# MB1315A.net
KiCad netlist of a schematic drawn in Altium Designer
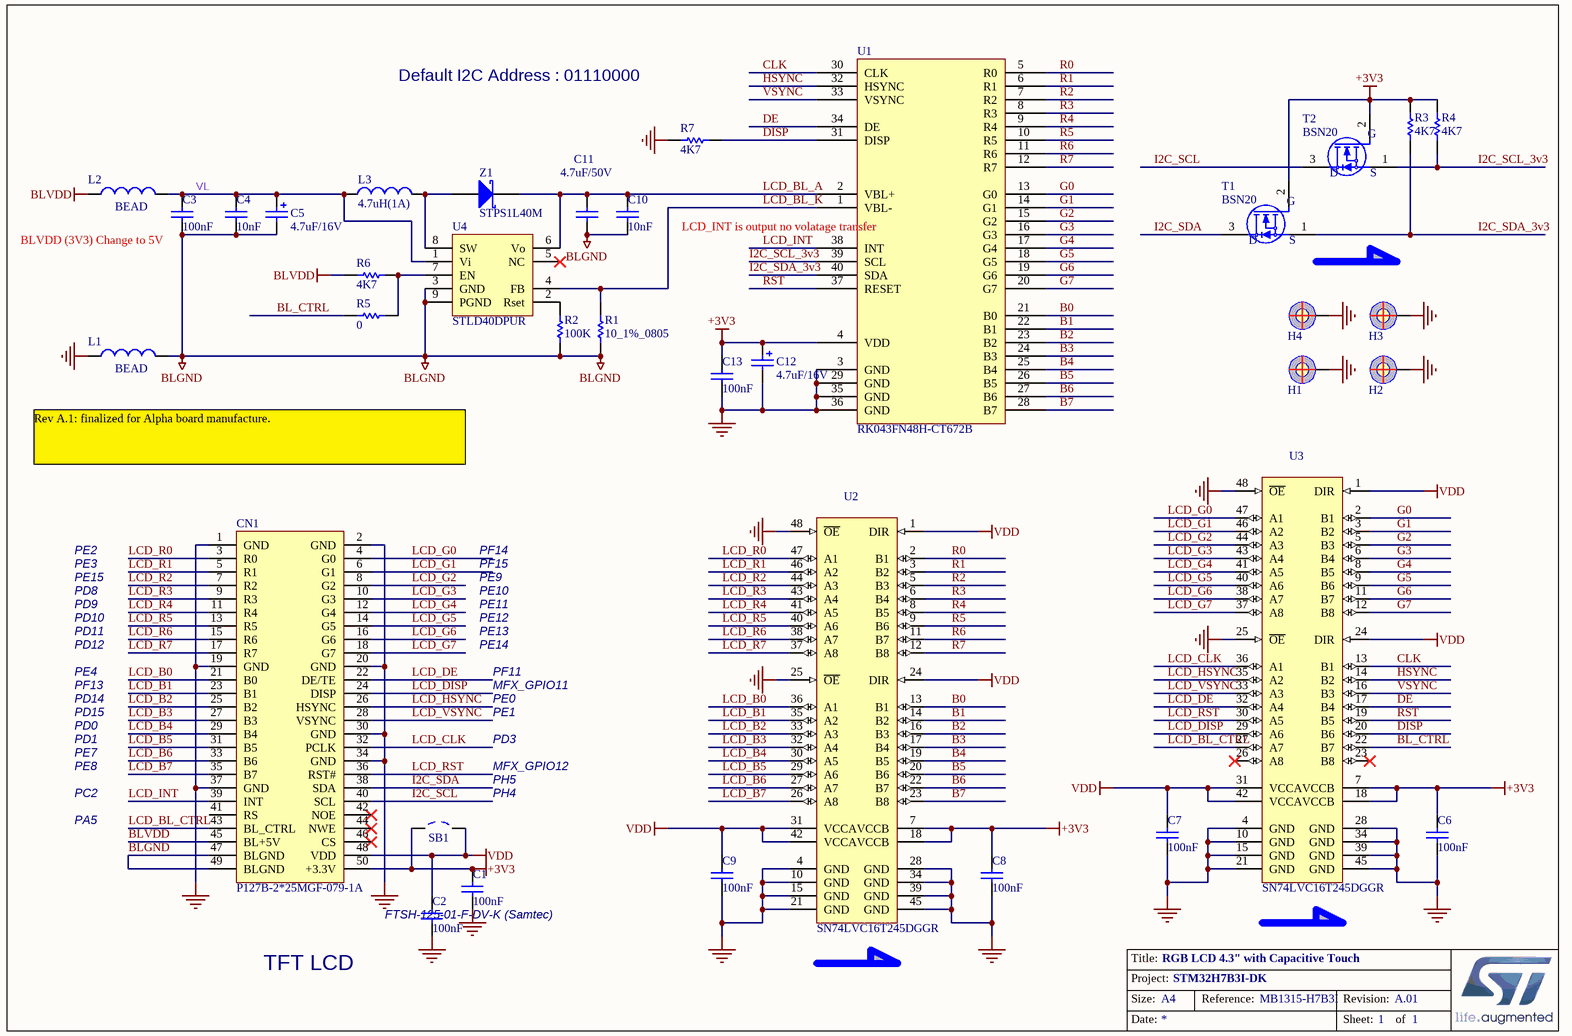
[diagram p0: MB1315A.SchDoc]

(export (version "E")
  (design (tool "Eeschema 10.0.6"))
  (components
    (comp (ref "C1")
      (value "100nF")
      (footprint "0603C")
      (description "Capacitor")
      (fields (field (name "PUBLISHER") "Altium Limited"))
      (libsource (lib "Miscellaneous Devices") (part "CAP"))
    )
    (comp (ref "C2")
      (value "100nF")
      (footprint "0603C")
      (description "Capacitor")
      (fields (field (name "PUBLISHER") "Altium Limited"))
      (libsource (lib "Miscellaneous Devices") (part "CAP"))
    )
    (comp (ref "C3")
      (value "100nF")
      (footprint "0603C")
      (description "Capacitor,100nF,16V,X7R,10%,0603,YAGEO")
      (libsource (lib "MCD_TOOLS") (part "Cap_100nF_X7R_10%_0603"))
    )
    (comp (ref "C4")
      (value "10nF")
      (footprint "0603C")
      (description "Capacitor,10nF,50V,X7R,10%,0603,YAGEO")
      (libsource (lib "MCD_TOOLS") (part "Cap_10nF_X7R_10%_0603"))
    )
    (comp (ref "C5")
      (value "4.7uF/16V")
      (footprint "1206C")
      (description "Polarized Capacitor (Radial)")
      (fields (field (name "PUBLISHER") "Altium Limited"))
      (libsource (lib "Miscellaneous Devices") (part "Cap Pol1"))
    )
    (comp (ref "C6")
      (value "100nF")
      (footprint "0603C")
      (description "Capacitor")
      (fields (field (name "PUBLISHER") "Altium Limited"))
      (libsource (lib "Miscellaneous Devices") (part "CAP"))
    )
    (comp (ref "C7")
      (value "100nF")
      (footprint "0603C")
      (description "Capacitor")
      (fields (field (name "PUBLISHER") "Altium Limited"))
      (libsource (lib "Miscellaneous Devices") (part "CAP"))
    )
    (comp (ref "C8")
      (value "100nF")
      (footprint "0603C")
      (description "Capacitor")
      (fields (field (name "PUBLISHER") "Altium Limited"))
      (libsource (lib "Miscellaneous Devices") (part "CAP"))
    )
    (comp (ref "C9")
      (value "100nF")
      (footprint "0603C")
      (description "Capacitor")
      (fields (field (name "PUBLISHER") "Altium Limited"))
      (libsource (lib "Miscellaneous Devices") (part "CAP"))
    )
    (comp (ref "C10")
      (value "10nF")
      (footprint "0603C")
      (description "Capacitor,10nF,50V,X7R,10%,0603,YAGEO")
      (libsource (lib "MCD_TOOLS") (part "Cap_10nF_X7R_10%_0603"))
    )
    (comp (ref "C11")
      (value "4.7uF/50V")
      (footprint "1206C")
      (description "Capacitor")
      (fields (field (name "PUBLISHER") "Altium Limited"))
      (libsource (lib "Miscellaneous Devices") (part "CAP"))
    )
    (comp (ref "C12")
      (value "4.7uF/16V")
      (footprint "1206C")
      (description "Polarized Capacitor (Radial)")
      (fields (field (name "PUBLISHER") "Altium Limited"))
      (libsource (lib "Miscellaneous Devices") (part "Cap Pol1"))
    )
    (comp (ref "C13")
      (value "100nF")
      (footprint "0603C")
      (description "Capacitor")
      (fields (field (name "PUBLISHER") "Altium Limited"))
      (libsource (lib "Miscellaneous Devices") (part "CAP"))
    )
    (comp (ref "CN1")
      (value "P127B-2*25MGF-079-1A")
      (footprint "FTSH-125-01-F-DV")
      (description "TFT LCD connector")
      (fields (field (name "PUBLISHER") "Altium Limited"))
      (libsource (lib "MB1313") (part "Header 25X2"))
    )
    (comp (ref "H1")
      (value "POSITION HOLE")
      (footprint "HOLE_C9D4R5")
      (libsource (lib "mb1045") (part "POSITION HOLE"))
    )
    (comp (ref "H2")
      (value "POSITION HOLE")
      (footprint "HOLE_C9D4R5")
      (libsource (lib "mb1045") (part "POSITION HOLE"))
    )
    (comp (ref "H3")
      (value "POSITION HOLE")
      (footprint "HOLE_C9D4R5")
      (libsource (lib "mb1045") (part "POSITION HOLE"))
    )
    (comp (ref "H4")
      (value "POSITION HOLE")
      (footprint "HOLE_C9D4R5")
      (libsource (lib "mb1045") (part "POSITION HOLE"))
    )
    (comp (ref "L1")
      (value "BEAD")
      (footprint "0603L")
      (description "Inductor")
      (fields (field (name "PUBLISHER") "Altium Limited"))
      (libsource (lib "Miscellaneous Devices") (part "Inductor"))
    )
    (comp (ref "L2")
      (value "BEAD")
      (footprint "0603L")
      (description "Inductor")
      (fields (field (name "PUBLISHER") "Altium Limited"))
      (libsource (lib "Miscellaneous Devices") (part "Inductor"))
    )
    (comp (ref "L3")
      (value "4.7uH(1A)")
      (footprint "1210L")
      (description "Inductor")
      (libsource (lib "Miscellaneous Devices") (part "Inductor"))
    )
    (comp (ref "R1")
      (value "10_1%_0805")
      (footprint "0805R")
      (description "Resistor,10,0805,1%,Stackpole,1/4W")
      (libsource (lib "MCD_TOOLS") (part "Res_10_1%_0805"))
    )
    (comp (ref "R2")
      (value "100K")
      (footprint "0603R")
      (description "Resistor,100K,0603,1%,YAGEO")
      (libsource (lib "MCD_TOOLS_RESISTOR") (part "Res_1K_1%_0603"))
    )
    (comp (ref "R3")
      (value "4K7")
      (footprint "0603R")
      (description "Resistor,4.7K,0603,1%,YAGEO")
      (libsource (lib "MCD_TOOLS_RESISTOR") (part "Res_1K_1%_0603"))
    )
    (comp (ref "R4")
      (value "4K7")
      (footprint "0603R")
      (description "Resistor,4.7K,0603,1%,YAGEO")
      (libsource (lib "MCD_TOOLS_RESISTOR") (part "Res_1K_1%_0603"))
    )
    (comp (ref "R5")
      (value "0")
      (footprint "0603R")
      (description "Resistor,0K,0603,1%,YAGEO")
      (libsource (lib "MCD_TOOLS_RESISTOR") (part "Res_1K_1%_0603"))
    )
    (comp (ref "R6")
      (value "4K7")
      (footprint "0603R")
      (description "Resistor,4.7K,0603,1%,YAGEO")
      (libsource (lib "MCD_TOOLS_RESISTOR") (part "Res_1K_1%_0603"))
    )
    (comp (ref "R7")
      (value "4K7")
      (footprint "0603R")
      (description "Resistor,4.7K,0603,1%,YAGEO")
      (libsource (lib "MCD_TOOLS_RESISTOR") (part "Res_1K_1%_0603"))
    )
    (comp (ref "SB1")
      (value "Solder Bridge OFF")
      (footprint "SB_0603")
      (libsource (lib "MCD_TOOLS") (part "SB_OFF"))
    )
    (comp (ref "T1") (value "BSN20") (footprint "SOT23-213") (libsource (lib "MB525") (part "2N7000")))
    (comp (ref "T2") (value "BSN20") (footprint "SOT23-213") (libsource (lib "MB525") (part "2N7000")))
    (comp (ref "U1")
      (value "RK043FN48H-CT672B")
      (footprint "LCD_RK043FN48H-CT672B")
      (description "4.3 inch TFT 480*272 pixels with LED Backlight and Capacitive touch panel, high luminance")
      (libsource (lib "MCD_TOOLS") (part "RK043FN48H-CT672B"))
    )
    (comp (ref "U2")
      (value "SN74LVC16T245DGGR")
      (footprint "TSSOP48_0R5_12R5X8R1")
      (libsource (lib "MB964_1") (part "SN74LVC16T245"))
    )
    (comp (ref "U3")
      (value "SN74LVC16T245DGGR")
      (footprint "TSSOP48_0R5_12R5X8R1")
      (libsource (lib "MB964_1") (part "SN74LVC16T245"))
    )
    (comp (ref "U4")
      (value "STLD40DPUR")
      (footprint "SON8_0R65_3X3")
      (description "White LED power supply for large display backlight, QFN8")
      (libsource (lib "MCD_TOOLS") (part "STLD40DPUR"))
    )
    (comp (ref "Z1")
      (value "STPS1L40M")
      (footprint "DO-216AA")
      (description "Schottky Diode")
      (fields (field (name "PUBLISHER") "Altium Limited"))
      (libsource (lib "Miscellaneous Devices") (part "D Schottky"))
    )
  )
  (nets
    (net (code "1") (name "+3V3") (class "Default")
      (node (ref "C1") (pin "2") (pinfunction "2_2") (pintype "passive"))
      (node (ref "C12") (pin "1") (pinfunction "1_1") (pintype "passive"))
      (node (ref "C13") (pin "2") (pinfunction "2_2") (pintype "passive"))
      (node (ref "C6") (pin "2") (pinfunction "2_2") (pintype "passive"))
      (node (ref "C8") (pin "2") (pinfunction "2_2") (pintype "passive"))
      (node (ref "CN1") (pin "50") (pinfunction "+3.3V_50") (pintype "passive"))
      (node (ref "R3") (pin "2") (pinfunction "2_2") (pintype "passive"))
      (node (ref "R4") (pin "2") (pinfunction "2_2") (pintype "passive"))
      (node (ref "SB1") (pin "1") (pinfunction "1_1") (pintype "passive"))
      (node (ref "T1") (pin "2") (pinfunction "G_2") (pintype "passive"))
      (node (ref "T2") (pin "2") (pinfunction "G_2") (pintype "passive"))
      (node (ref "U1") (pin "4") (pinfunction "VDD_4") (pintype "passive"))
      (node (ref "U2") (pin "18") (pinfunction "VCCB_18") (pintype "power_in"))
      (node (ref "U2") (pin "7") (pinfunction "VCCB_7") (pintype "power_in"))
      (node (ref "U3") (pin "18") (pinfunction "VCCB_18") (pintype "power_in"))
      (node (ref "U3") (pin "7") (pinfunction "VCCB_7") (pintype "power_in"))
    )
    (net (code "2") (name "/B0") (class "Default")
      (node (ref "U1") (pin "21") (pinfunction "B0_21") (pintype "passive"))
      (node (ref "U2") (pin "13") (pinfunction "B1_13") (pintype "bidirectional"))
    )
    (net (code "3") (name "/B1") (class "Default")
      (node (ref "U1") (pin "22") (pinfunction "B1_22") (pintype "passive"))
      (node (ref "U2") (pin "14") (pinfunction "B2_14") (pintype "bidirectional"))
    )
    (net (code "4") (name "/B2") (class "Default")
      (node (ref "U1") (pin "23") (pinfunction "B2_23") (pintype "passive"))
      (node (ref "U2") (pin "16") (pinfunction "B3_16") (pintype "bidirectional"))
    )
    (net (code "5") (name "/B3") (class "Default")
      (node (ref "U1") (pin "24") (pinfunction "B3_24") (pintype "passive"))
      (node (ref "U2") (pin "17") (pinfunction "B4_17") (pintype "bidirectional"))
    )
    (net (code "6") (name "/B4") (class "Default")
      (node (ref "U1") (pin "25") (pinfunction "B4_25") (pintype "passive"))
      (node (ref "U2") (pin "19") (pinfunction "B5_19") (pintype "bidirectional"))
    )
    (net (code "7") (name "/B5") (class "Default")
      (node (ref "U1") (pin "26") (pinfunction "B5_26") (pintype "passive"))
      (node (ref "U2") (pin "20") (pinfunction "B6_20") (pintype "bidirectional"))
    )
    (net (code "8") (name "/B6") (class "Default")
      (node (ref "U1") (pin "27") (pinfunction "B6_27") (pintype "passive"))
      (node (ref "U2") (pin "22") (pinfunction "B7_22") (pintype "bidirectional"))
    )
    (net (code "9") (name "/B7") (class "Default")
      (node (ref "U1") (pin "28") (pinfunction "B7_28") (pintype "passive"))
      (node (ref "U2") (pin "23") (pinfunction "B8_23") (pintype "bidirectional"))
    )
    (net (code "10") (name "/BL_CTRL") (class "Default")
      (node (ref "R5") (pin "2") (pinfunction "2_2") (pintype "passive"))
      (node (ref "U3") (pin "22") (pinfunction "B7_22") (pintype "bidirectional"))
    )
    (net (code "11") (name "/CLK") (class "Default")
      (node (ref "U1") (pin "30") (pinfunction "CLK_30") (pintype "passive"))
      (node (ref "U3") (pin "13") (pinfunction "B1_13") (pintype "bidirectional"))
    )
    (net (code "12") (name "/DE") (class "Default")
      (node (ref "U1") (pin "34") (pinfunction "DE_34") (pintype "passive"))
      (node (ref "U3") (pin "17") (pinfunction "B4_17") (pintype "bidirectional"))
    )
    (net (code "13") (name "/DISP") (class "Default")
      (node (ref "R7") (pin "1") (pinfunction "1_1") (pintype "passive"))
      (node (ref "U1") (pin "31") (pinfunction "DISP_31") (pintype "passive"))
      (node (ref "U3") (pin "20") (pinfunction "B6_20") (pintype "bidirectional"))
    )
    (net (code "14") (name "/G0") (class "Default")
      (node (ref "U1") (pin "13") (pinfunction "G0_13") (pintype "passive"))
      (node (ref "U3") (pin "2") (pinfunction "B1_2") (pintype "bidirectional"))
    )
    (net (code "15") (name "/G1") (class "Default")
      (node (ref "U1") (pin "14") (pinfunction "G1_14") (pintype "passive"))
      (node (ref "U3") (pin "3") (pinfunction "B2_3") (pintype "bidirectional"))
    )
    (net (code "16") (name "/G2") (class "Default")
      (node (ref "U1") (pin "15") (pinfunction "G2_15") (pintype "passive"))
      (node (ref "U3") (pin "5") (pinfunction "B3_5") (pintype "bidirectional"))
    )
    (net (code "17") (name "/G3") (class "Default")
      (node (ref "U1") (pin "16") (pinfunction "G3_16") (pintype "passive"))
      (node (ref "U3") (pin "6") (pinfunction "B4_6") (pintype "bidirectional"))
    )
    (net (code "18") (name "/G4") (class "Default")
      (node (ref "U1") (pin "17") (pinfunction "G4_17") (pintype "passive"))
      (node (ref "U3") (pin "8") (pinfunction "B5_8") (pintype "bidirectional"))
    )
    (net (code "19") (name "/G5") (class "Default")
      (node (ref "U1") (pin "18") (pinfunction "G5_18") (pintype "passive"))
      (node (ref "U3") (pin "9") (pinfunction "B6_9") (pintype "bidirectional"))
    )
    (net (code "20") (name "/G6") (class "Default")
      (node (ref "U1") (pin "19") (pinfunction "G6_19") (pintype "passive"))
      (node (ref "U3") (pin "11") (pinfunction "B7_11") (pintype "bidirectional"))
    )
    (net (code "21") (name "/G7") (class "Default")
      (node (ref "U1") (pin "20") (pinfunction "G7_20") (pintype "passive"))
      (node (ref "U3") (pin "12") (pinfunction "B8_12") (pintype "bidirectional"))
    )
    (net (code "22") (name "/HSYNC") (class "Default")
      (node (ref "U1") (pin "32") (pinfunction "HSYNC_32") (pintype "passive"))
      (node (ref "U3") (pin "14") (pinfunction "B2_14") (pintype "bidirectional"))
    )
    (net (code "23") (name "/I2C_SCL") (class "Default")
      (node (ref "CN1") (pin "40") (pinfunction "SCL_40") (pintype "passive"))
      (node (ref "T2") (pin "3") (pinfunction "D_3") (pintype "passive"))
    )
    (net (code "24") (name "/I2C_SCL_3v3") (class "Default")
      (node (ref "R4") (pin "1") (pinfunction "1_1") (pintype "passive"))
      (node (ref "T2") (pin "1") (pinfunction "S_1") (pintype "passive"))
      (node (ref "U1") (pin "39") (pinfunction "SCL_39") (pintype "passive"))
    )
    (net (code "25") (name "/I2C_SDA") (class "Default")
      (node (ref "CN1") (pin "38") (pinfunction "SDA_38") (pintype "passive"))
      (node (ref "T1") (pin "3") (pinfunction "D_3") (pintype "passive"))
    )
    (net (code "26") (name "/I2C_SDA_3v3") (class "Default")
      (node (ref "R3") (pin "1") (pinfunction "1_1") (pintype "passive"))
      (node (ref "T1") (pin "1") (pinfunction "S_1") (pintype "passive"))
      (node (ref "U1") (pin "40") (pinfunction "SDA_40") (pintype "passive"))
    )
    (net (code "27") (name "/LCD_B0") (class "Default")
      (node (ref "CN1") (pin "21") (pinfunction "B0_21") (pintype "passive"))
      (node (ref "U2") (pin "36") (pinfunction "A1_36") (pintype "bidirectional"))
    )
    (net (code "28") (name "/LCD_B1") (class "Default")
      (node (ref "CN1") (pin "23") (pinfunction "B1_23") (pintype "passive"))
      (node (ref "U2") (pin "35") (pinfunction "A2_35") (pintype "bidirectional"))
    )
    (net (code "29") (name "/LCD_B2") (class "Default")
      (node (ref "CN1") (pin "25") (pinfunction "B2_25") (pintype "passive"))
      (node (ref "U2") (pin "33") (pinfunction "A3_33") (pintype "bidirectional"))
    )
    (net (code "30") (name "/LCD_B3") (class "Default")
      (node (ref "CN1") (pin "27") (pinfunction "B3_27") (pintype "passive"))
      (node (ref "U2") (pin "32") (pinfunction "A4_32") (pintype "bidirectional"))
    )
    (net (code "31") (name "/LCD_B4") (class "Default")
      (node (ref "CN1") (pin "29") (pinfunction "B4_29") (pintype "passive"))
      (node (ref "U2") (pin "30") (pinfunction "A5_30") (pintype "bidirectional"))
    )
    (net (code "32") (name "/LCD_B5") (class "Default")
      (node (ref "CN1") (pin "31") (pinfunction "B5_31") (pintype "passive"))
      (node (ref "U2") (pin "29") (pinfunction "A6_29") (pintype "bidirectional"))
    )
    (net (code "33") (name "/LCD_B6") (class "Default")
      (node (ref "CN1") (pin "33") (pinfunction "B6_33") (pintype "passive"))
      (node (ref "U2") (pin "27") (pinfunction "A7_27") (pintype "bidirectional"))
    )
    (net (code "34") (name "/LCD_B7") (class "Default")
      (node (ref "CN1") (pin "35") (pinfunction "B7_35") (pintype "passive"))
      (node (ref "U2") (pin "26") (pinfunction "A8_26") (pintype "bidirectional"))
    )
    (net (code "35") (name "/LCD_BL_A") (class "Default")
      (node (ref "C10") (pin "2") (pinfunction "2_2") (pintype "passive"))
      (node (ref "C11") (pin "1") (pinfunction "1_1") (pintype "passive"))
      (node (ref "U1") (pin "2") (pinfunction "VBL+_2") (pintype "passive"))
      (node (ref "U4") (pin "6") (pinfunction "Vo_6") (pintype "passive"))
      (node (ref "Z1") (pin "2") (pinfunction "K_2") (pintype "passive"))
    )
    (net (code "36") (name "/LCD_BL_CTRL") (class "Default")
      (node (ref "CN1") (pin "43") (pinfunction "BL_CTRL_43") (pintype "passive"))
      (node (ref "U3") (pin "27") (pinfunction "A7_27") (pintype "bidirectional"))
    )
    (net (code "37") (name "/LCD_BL_K") (class "Default")
      (node (ref "R1") (pin "2") (pinfunction "2_2") (pintype "passive"))
      (node (ref "U1") (pin "1") (pinfunction "VBL-_1") (pintype "passive"))
      (node (ref "U4") (pin "4") (pinfunction "FB_4") (pintype "passive"))
    )
    (net (code "38") (name "/LCD_CLK") (class "Default")
      (node (ref "CN1") (pin "32") (pinfunction "PCLK_32") (pintype "passive"))
      (node (ref "U3") (pin "36") (pinfunction "A1_36") (pintype "bidirectional"))
    )
    (net (code "39") (name "/LCD_DE") (class "Default")
      (node (ref "CN1") (pin "22") (pinfunction "DE/TE_22") (pintype "passive"))
      (node (ref "U3") (pin "32") (pinfunction "A4_32") (pintype "bidirectional"))
    )
    (net (code "40") (name "/LCD_DISP") (class "Default")
      (node (ref "CN1") (pin "24") (pinfunction "DISP_24") (pintype "passive"))
      (node (ref "U3") (pin "29") (pinfunction "A6_29") (pintype "bidirectional"))
    )
    (net (code "41") (name "/LCD_G0") (class "Default")
      (node (ref "CN1") (pin "4") (pinfunction "G0_4") (pintype "passive"))
      (node (ref "U3") (pin "47") (pinfunction "A1_47") (pintype "bidirectional"))
    )
    (net (code "42") (name "/LCD_G1") (class "Default")
      (node (ref "CN1") (pin "6") (pinfunction "G1_6") (pintype "passive"))
      (node (ref "U3") (pin "46") (pinfunction "A2_46") (pintype "bidirectional"))
    )
    (net (code "43") (name "/LCD_G2") (class "Default")
      (node (ref "CN1") (pin "8") (pinfunction "G2_8") (pintype "passive"))
      (node (ref "U3") (pin "44") (pinfunction "A3_44") (pintype "bidirectional"))
    )
    (net (code "44") (name "/LCD_G3") (class "Default")
      (node (ref "CN1") (pin "10") (pinfunction "G3_10") (pintype "passive"))
      (node (ref "U3") (pin "43") (pinfunction "A4_43") (pintype "bidirectional"))
    )
    (net (code "45") (name "/LCD_G4") (class "Default")
      (node (ref "CN1") (pin "12") (pinfunction "G4_12") (pintype "passive"))
      (node (ref "U3") (pin "41") (pinfunction "A5_41") (pintype "bidirectional"))
    )
    (net (code "46") (name "/LCD_G5") (class "Default")
      (node (ref "CN1") (pin "14") (pinfunction "G5_14") (pintype "passive"))
      (node (ref "U3") (pin "40") (pinfunction "A6_40") (pintype "bidirectional"))
    )
    (net (code "47") (name "/LCD_G6") (class "Default")
      (node (ref "CN1") (pin "16") (pinfunction "G6_16") (pintype "passive"))
      (node (ref "U3") (pin "38") (pinfunction "A7_38") (pintype "bidirectional"))
    )
    (net (code "48") (name "/LCD_G7") (class "Default")
      (node (ref "CN1") (pin "18") (pinfunction "G7_18") (pintype "passive"))
      (node (ref "U3") (pin "37") (pinfunction "A8_37") (pintype "bidirectional"))
    )
    (net (code "49") (name "/LCD_HSYNC") (class "Default")
      (node (ref "CN1") (pin "26") (pinfunction "HSYNC_26") (pintype "passive"))
      (node (ref "U3") (pin "35") (pinfunction "A2_35") (pintype "bidirectional"))
    )
    (net (code "50") (name "/LCD_INT") (class "Default")
      (node (ref "CN1") (pin "39") (pinfunction "INT_39") (pintype "passive"))
      (node (ref "U1") (pin "38") (pinfunction "INT_38") (pintype "passive"))
    )
    (net (code "51") (name "/LCD_R0") (class "Default")
      (node (ref "CN1") (pin "3") (pinfunction "R0_3") (pintype "passive"))
      (node (ref "U2") (pin "47") (pinfunction "A1_47") (pintype "bidirectional"))
    )
    (net (code "52") (name "/LCD_R1") (class "Default")
      (node (ref "CN1") (pin "5") (pinfunction "R1_5") (pintype "passive"))
      (node (ref "U2") (pin "46") (pinfunction "A2_46") (pintype "bidirectional"))
    )
    (net (code "53") (name "/LCD_R2") (class "Default")
      (node (ref "CN1") (pin "7") (pinfunction "R2_7") (pintype "passive"))
      (node (ref "U2") (pin "44") (pinfunction "A3_44") (pintype "bidirectional"))
    )
    (net (code "54") (name "/LCD_R3") (class "Default")
      (node (ref "CN1") (pin "9") (pinfunction "R3_9") (pintype "passive"))
      (node (ref "U2") (pin "43") (pinfunction "A4_43") (pintype "bidirectional"))
    )
    (net (code "55") (name "/LCD_R4") (class "Default")
      (node (ref "CN1") (pin "11") (pinfunction "R4_11") (pintype "passive"))
      (node (ref "U2") (pin "41") (pinfunction "A5_41") (pintype "bidirectional"))
    )
    (net (code "56") (name "/LCD_R5") (class "Default")
      (node (ref "CN1") (pin "13") (pinfunction "R5_13") (pintype "passive"))
      (node (ref "U2") (pin "40") (pinfunction "A6_40") (pintype "bidirectional"))
    )
    (net (code "57") (name "/LCD_R6") (class "Default")
      (node (ref "CN1") (pin "15") (pinfunction "R6_15") (pintype "passive"))
      (node (ref "U2") (pin "38") (pinfunction "A7_38") (pintype "bidirectional"))
    )
    (net (code "58") (name "/LCD_R7") (class "Default")
      (node (ref "CN1") (pin "17") (pinfunction "R7_17") (pintype "passive"))
      (node (ref "U2") (pin "37") (pinfunction "A8_37") (pintype "bidirectional"))
    )
    (net (code "59") (name "/LCD_RST") (class "Default")
      (node (ref "CN1") (pin "36") (pinfunction "RST#_36") (pintype "passive"))
      (node (ref "U3") (pin "30") (pinfunction "A5_30") (pintype "bidirectional"))
    )
    (net (code "60") (name "/LCD_VSYNC") (class "Default")
      (node (ref "CN1") (pin "28") (pinfunction "VSYNC_28") (pintype "passive"))
      (node (ref "U3") (pin "33") (pinfunction "A3_33") (pintype "bidirectional"))
    )
    (net (code "61") (name "/R0") (class "Default")
      (node (ref "U1") (pin "5") (pinfunction "R0_5") (pintype "passive"))
      (node (ref "U2") (pin "2") (pinfunction "B1_2") (pintype "bidirectional"))
    )
    (net (code "62") (name "/R1") (class "Default")
      (node (ref "U1") (pin "6") (pinfunction "R1_6") (pintype "passive"))
      (node (ref "U2") (pin "3") (pinfunction "B2_3") (pintype "bidirectional"))
    )
    (net (code "63") (name "/R2") (class "Default")
      (node (ref "U1") (pin "7") (pinfunction "R2_7") (pintype "passive"))
      (node (ref "U2") (pin "5") (pinfunction "B3_5") (pintype "bidirectional"))
    )
    (net (code "64") (name "/R3") (class "Default")
      (node (ref "U1") (pin "8") (pinfunction "R3_8") (pintype "passive"))
      (node (ref "U2") (pin "6") (pinfunction "B4_6") (pintype "bidirectional"))
    )
    (net (code "65") (name "/R4") (class "Default")
      (node (ref "U1") (pin "9") (pinfunction "R4_9") (pintype "passive"))
      (node (ref "U2") (pin "8") (pinfunction "B5_8") (pintype "bidirectional"))
    )
    (net (code "66") (name "/R5") (class "Default")
      (node (ref "U1") (pin "10") (pinfunction "R5_10") (pintype "passive"))
      (node (ref "U2") (pin "9") (pinfunction "B6_9") (pintype "bidirectional"))
    )
    (net (code "67") (name "/R6") (class "Default")
      (node (ref "U1") (pin "11") (pinfunction "R6_11") (pintype "passive"))
      (node (ref "U2") (pin "11") (pinfunction "B7_11") (pintype "bidirectional"))
    )
    (net (code "68") (name "/R7") (class "Default")
      (node (ref "U1") (pin "12") (pinfunction "R7_12") (pintype "passive"))
      (node (ref "U2") (pin "12") (pinfunction "B8_12") (pintype "bidirectional"))
    )
    (net (code "69") (name "/RST") (class "Default")
      (node (ref "U1") (pin "37") (pinfunction "RESET_37") (pintype "passive"))
      (node (ref "U3") (pin "19") (pinfunction "B5_19") (pintype "bidirectional"))
    )
    (net (code "70") (name "/VL") (class "Default")
      (node (ref "C3") (pin "2") (pinfunction "2_2") (pintype "passive"))
      (node (ref "C4") (pin "2") (pinfunction "2_2") (pintype "passive"))
      (node (ref "C5") (pin "1") (pinfunction "1_1") (pintype "passive"))
      (node (ref "L2") (pin "2") (pinfunction "2_2") (pintype "passive"))
      (node (ref "L3") (pin "1") (pinfunction "1_1") (pintype "passive"))
      (node (ref "U4") (pin "1") (pinfunction "Vi_1") (pintype "passive"))
    )
    (net (code "71") (name "/VSYNC") (class "Default")
      (node (ref "U1") (pin "33") (pinfunction "VSYNC_33") (pintype "passive"))
      (node (ref "U3") (pin "16") (pinfunction "B3_16") (pintype "bidirectional"))
    )
    (net (code "72") (name "BLGND") (class "Default")
      (node (ref "C10") (pin "1") (pinfunction "1_1") (pintype "passive"))
      (node (ref "C11") (pin "2") (pinfunction "2_2") (pintype "passive"))
      (node (ref "C3") (pin "1") (pinfunction "1_1") (pintype "passive"))
      (node (ref "C4") (pin "1") (pinfunction "1_1") (pintype "passive"))
      (node (ref "C5") (pin "2") (pinfunction "2_2") (pintype "passive"))
      (node (ref "CN1") (pin "47") (pinfunction "BLGND_47") (pintype "passive"))
      (node (ref "CN1") (pin "49") (pinfunction "BLGND_49") (pintype "passive"))
      (node (ref "L1") (pin "2") (pinfunction "2_2") (pintype "passive"))
      (node (ref "R1") (pin "1") (pinfunction "1_1") (pintype "passive"))
      (node (ref "R2") (pin "1") (pinfunction "1_1") (pintype "passive"))
      (node (ref "U4") (pin "3") (pinfunction "GND_3") (pintype "passive"))
      (node (ref "U4") (pin "9") (pinfunction "PGND_9") (pintype "passive"))
    )
    (net (code "73") (name "BLVDD") (class "Default")
      (node (ref "CN1") (pin "45") (pinfunction "BL+5V_45") (pintype "passive"))
      (node (ref "L2") (pin "1") (pinfunction "1_1") (pintype "passive"))
      (node (ref "R6") (pin "2") (pinfunction "2_2") (pintype "passive"))
    )
    (net (code "74") (name "GND") (class "Default")
      (node (ref "C1") (pin "1") (pinfunction "1_1") (pintype "passive"))
      (node (ref "C12") (pin "2") (pinfunction "2_2") (pintype "passive"))
      (node (ref "C13") (pin "1") (pinfunction "1_1") (pintype "passive"))
      (node (ref "C2") (pin "1") (pinfunction "1_1") (pintype "passive"))
      (node (ref "C6") (pin "1") (pinfunction "1_1") (pintype "passive"))
      (node (ref "C7") (pin "1") (pinfunction "1_1") (pintype "passive"))
      (node (ref "C8") (pin "1") (pinfunction "1_1") (pintype "passive"))
      (node (ref "C9") (pin "1") (pinfunction "1_1") (pintype "passive"))
      (node (ref "CN1") (pin "1") (pinfunction "GND_1") (pintype "passive"))
      (node (ref "CN1") (pin "19") (pinfunction "GND_19") (pintype "passive"))
      (node (ref "CN1") (pin "2") (pinfunction "GND_2") (pintype "passive"))
      (node (ref "CN1") (pin "20") (pinfunction "GND_20") (pintype "passive"))
      (node (ref "CN1") (pin "30") (pinfunction "GND_30") (pintype "passive"))
      (node (ref "CN1") (pin "34") (pinfunction "GND_34") (pintype "passive"))
      (node (ref "CN1") (pin "37") (pinfunction "GND_37") (pintype "passive"))
      (node (ref "H1") (pin "1") (pinfunction "1_1") (pintype "passive"))
      (node (ref "H2") (pin "1") (pinfunction "1_1") (pintype "passive"))
      (node (ref "H3") (pin "1") (pinfunction "1_1") (pintype "passive"))
      (node (ref "H4") (pin "1") (pinfunction "1_1") (pintype "passive"))
      (node (ref "L1") (pin "1") (pinfunction "1_1") (pintype "passive"))
      (node (ref "R7") (pin "2") (pinfunction "2_2") (pintype "passive"))
      (node (ref "U1") (pin "29") (pinfunction "GND_29") (pintype "passive"))
      (node (ref "U1") (pin "3") (pinfunction "GND_3") (pintype "passive"))
      (node (ref "U1") (pin "35") (pinfunction "GND_35") (pintype "passive"))
      (node (ref "U1") (pin "36") (pinfunction "GND_36") (pintype "passive"))
      (node (ref "U2") (pin "10") (pinfunction "GND_10") (pintype "power_in"))
      (node (ref "U2") (pin "15") (pinfunction "GND_15") (pintype "power_in"))
      (node (ref "U2") (pin "21") (pinfunction "GND_21") (pintype "power_in"))
      (node (ref "U2") (pin "25") (pinfunction "~{OE}_25") (pintype "input"))
      (node (ref "U2") (pin "28") (pinfunction "GND_28") (pintype "power_in"))
      (node (ref "U2") (pin "34") (pinfunction "GND_34") (pintype "power_in"))
      (node (ref "U2") (pin "39") (pinfunction "GND_39") (pintype "power_in"))
      (node (ref "U2") (pin "4") (pinfunction "GND_4") (pintype "power_in"))
      (node (ref "U2") (pin "45") (pinfunction "GND_45") (pintype "power_in"))
      (node (ref "U2") (pin "48") (pinfunction "~{OE}_48") (pintype "input"))
      (node (ref "U3") (pin "10") (pinfunction "GND_10") (pintype "power_in"))
      (node (ref "U3") (pin "15") (pinfunction "GND_15") (pintype "power_in"))
      (node (ref "U3") (pin "21") (pinfunction "GND_21") (pintype "power_in"))
      (node (ref "U3") (pin "25") (pinfunction "~{OE}_25") (pintype "input"))
      (node (ref "U3") (pin "28") (pinfunction "GND_28") (pintype "power_in"))
      (node (ref "U3") (pin "34") (pinfunction "GND_34") (pintype "power_in"))
      (node (ref "U3") (pin "39") (pinfunction "GND_39") (pintype "power_in"))
      (node (ref "U3") (pin "4") (pinfunction "GND_4") (pintype "power_in"))
      (node (ref "U3") (pin "45") (pinfunction "GND_45") (pintype "power_in"))
      (node (ref "U3") (pin "48") (pinfunction "~{OE}_48") (pintype "input"))
    )
    (net (code "75") (name "Net-(U4-EN)") (class "Default")
      (node (ref "R5") (pin "1") (pinfunction "1_1") (pintype "passive"))
      (node (ref "R6") (pin "1") (pinfunction "1_1") (pintype "passive"))
      (node (ref "U4") (pin "7") (pinfunction "EN_7") (pintype "passive"))
    )
    (net (code "76") (name "Net-(U4-Rset)") (class "Default")
      (node (ref "R2") (pin "2") (pinfunction "2_2") (pintype "passive"))
      (node (ref "U4") (pin "2") (pinfunction "Rset_2") (pintype "passive"))
    )
    (net (code "77") (name "Net-(U4-SW)") (class "Default")
      (node (ref "L3") (pin "2") (pinfunction "2_2") (pintype "passive"))
      (node (ref "U4") (pin "8") (pinfunction "SW_8") (pintype "passive"))
      (node (ref "Z1") (pin "1") (pinfunction "A_1") (pintype "passive"))
    )
    (net (code "78") (name "VDD") (class "Default")
      (node (ref "C2") (pin "2") (pinfunction "2_2") (pintype "passive"))
      (node (ref "C7") (pin "2") (pinfunction "2_2") (pintype "passive"))
      (node (ref "C9") (pin "2") (pinfunction "2_2") (pintype "passive"))
      (node (ref "CN1") (pin "48") (pinfunction "VDD_48") (pintype "passive"))
      (node (ref "SB1") (pin "2") (pinfunction "2_2") (pintype "passive"))
      (node (ref "U2") (pin "1") (pinfunction "DIR_1") (pintype "input"))
      (node (ref "U2") (pin "24") (pinfunction "DIR_24") (pintype "input"))
      (node (ref "U2") (pin "31") (pinfunction "VCCA_31") (pintype "power_in"))
      (node (ref "U2") (pin "42") (pinfunction "VCCA_42") (pintype "power_in"))
      (node (ref "U3") (pin "1") (pinfunction "DIR_1") (pintype "input"))
      (node (ref "U3") (pin "24") (pinfunction "DIR_24") (pintype "input"))
      (node (ref "U3") (pin "31") (pinfunction "VCCA_31") (pintype "power_in"))
      (node (ref "U3") (pin "42") (pinfunction "VCCA_42") (pintype "power_in"))
    )
    (net (code "79") (name "unconnected-(CN1-CS-Pad46)") (class "Default")
      (node (ref "CN1") (pin "46") (pinfunction "CS_46") (pintype "passive+no_connect"))
    )
    (net (code "80") (name "unconnected-(CN1-NOE-Pad42)") (class "Default")
      (node (ref "CN1") (pin "42") (pinfunction "NOE_42") (pintype "passive+no_connect"))
    )
    (net (code "81") (name "unconnected-(CN1-NWE-Pad44)") (class "Default")
      (node (ref "CN1") (pin "44") (pinfunction "NWE_44") (pintype "passive+no_connect"))
    )
    (net (code "82") (name "unconnected-(CN1-RS-Pad41)") (class "Default")
      (node (ref "CN1") (pin "41") (pinfunction "RS_41") (pintype "passive"))
    )
    (net (code "83") (name "unconnected-(U3-A8-Pad26)") (class "Default")
      (node (ref "U3") (pin "26") (pinfunction "A8_26") (pintype "bidirectional+no_connect"))
    )
    (net (code "84") (name "unconnected-(U3-B8-Pad23)") (class "Default")
      (node (ref "U3") (pin "23") (pinfunction "B8_23") (pintype "bidirectional+no_connect"))
    )
    (net (code "85") (name "unconnected-(U4-NC-Pad5)") (class "Default")
      (node (ref "U4") (pin "5") (pinfunction "NC_5") (pintype "passive+no_connect"))
    )
  )
)
